# main.net
KiCad netlist of a schematic drawn in EAGLE
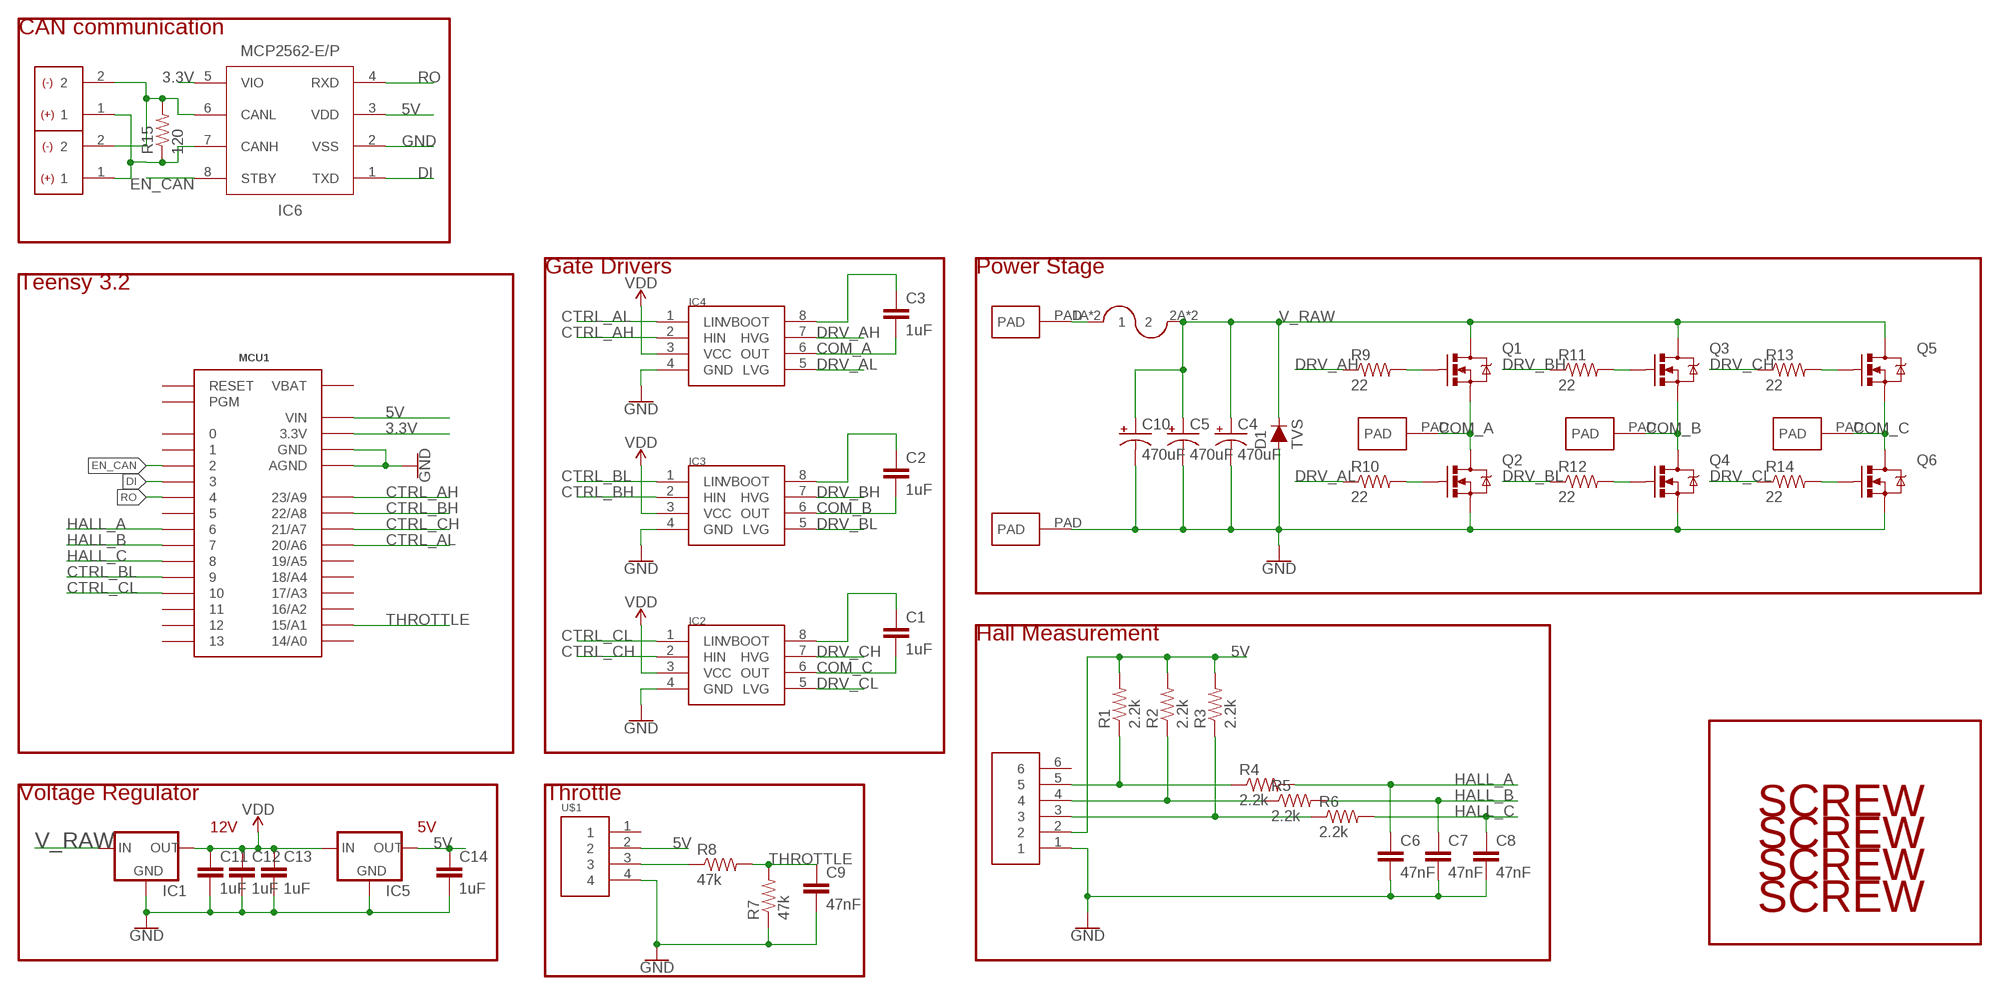
[diagram p0: schematic, sheet 1]

(export (version "E")
  (design (tool "Eeschema 10.0.6"))
  (components
    (comp (ref "C1")
      (value "1uF")
      (footprint "eagle-import:CAP-PTH-SMALL-KIT")
      (libsource (lib "eagle-import") (part "CAPKIT"))
    )
    (comp (ref "C2")
      (value "1uF")
      (footprint "eagle-import:CAP-PTH-SMALL-KIT")
      (libsource (lib "eagle-import") (part "CAPKIT"))
    )
    (comp (ref "C3")
      (value "1uF")
      (footprint "eagle-import:CAP-PTH-SMALL-KIT")
      (libsource (lib "eagle-import") (part "CAPKIT"))
    )
    (comp (ref "C4")
      (value "470uF")
      (footprint "eagle-import:CPOL-RADIAL-5MM-10MM")
      (libsource (lib "eagle-import") (part "1000UF-RADIAL-5MM-25V-20%"))
    )
    (comp (ref "C5")
      (value "470uF")
      (footprint "eagle-import:CPOL-RADIAL-5MM-10MM")
      (libsource (lib "eagle-import") (part "1000UF-RADIAL-5MM-25V-20%"))
    )
    (comp (ref "C6")
      (value "47nF")
      (footprint "eagle-import:CAP-PTH-SMALL-KIT")
      (libsource (lib "eagle-import") (part "CAPKIT"))
    )
    (comp (ref "C7")
      (value "47nF")
      (footprint "eagle-import:CAP-PTH-SMALL-KIT")
      (libsource (lib "eagle-import") (part "CAPKIT"))
    )
    (comp (ref "C8")
      (value "47nF")
      (footprint "eagle-import:CAP-PTH-SMALL-KIT")
      (libsource (lib "eagle-import") (part "CAPKIT"))
    )
    (comp (ref "C9")
      (value "47nF")
      (footprint "eagle-import:CAP-PTH-SMALL-KIT")
      (libsource (lib "eagle-import") (part "CAPKIT"))
    )
    (comp (ref "C10")
      (value "470uF")
      (footprint "eagle-import:CPOL-RADIAL-5MM-10MM")
      (libsource (lib "eagle-import") (part "1000UF-RADIAL-5MM-25V-20%"))
    )
    (comp (ref "C11")
      (value "1uF")
      (footprint "eagle-import:CAP-PTH-SMALL-KIT")
      (libsource (lib "eagle-import") (part "CAPKIT"))
    )
    (comp (ref "C12")
      (value "1uF")
      (footprint "eagle-import:CAP-PTH-SMALL-KIT")
      (libsource (lib "eagle-import") (part "CAPKIT"))
    )
    (comp (ref "C13")
      (value "1uF")
      (footprint "eagle-import:CAP-PTH-SMALL-KIT")
      (libsource (lib "eagle-import") (part "CAPKIT"))
    )
    (comp (ref "C14")
      (value "1uF")
      (footprint "eagle-import:CAP-PTH-SMALL-KIT")
      (libsource (lib "eagle-import") (part "CAPKIT"))
    )
    (comp (ref "CAN1")
      (value "HEADER2")
      (footprint "eagle-import:2PINVALULOK")
      (libsource (lib "eagle-import") (part "HEADER2"))
    )
    (comp (ref "CAN2")
      (value "HEADER2")
      (footprint "eagle-import:2PINVALULOK")
      (libsource (lib "eagle-import") (part "HEADER2"))
    )
    (comp (ref "D1")
      (value "TVS")
      (footprint "eagle-import:DIODE-1N4001")
      (libsource (lib "eagle-import") (part "DIODE-PTH"))
    )
    (comp (ref "IC1")
      (value "V_REG_78XX")
      (footprint "eagle-import:V78W_BACKWARDS")
      (libsource (lib "eagle-import") (part "V_REG_78XX"))
    )
    (comp (ref "IC2")
      (value "L6387EDIP8")
      (footprint "eagle-import:DIP762W53P254L1092H508Q8B")
      (libsource (lib "eagle-import") (part "L6387EDIP8"))
    )
    (comp (ref "IC3")
      (value "L6387EDIP8")
      (footprint "eagle-import:DIP762W53P254L1092H508Q8B")
      (libsource (lib "eagle-import") (part "L6387EDIP8"))
    )
    (comp (ref "IC4")
      (value "L6387EDIP8")
      (footprint "eagle-import:DIP762W53P254L1092H508Q8B")
      (libsource (lib "eagle-import") (part "L6387EDIP8"))
    )
    (comp (ref "IC5")
      (value "V_REG_78XXTO-92_UNTESTED")
      (footprint "eagle-import:TO-92")
      (libsource (lib "eagle-import") (part "SparkFun-IC-Power_V_REG_78XXTO-92_UNTESTED"))
    )
    (comp (ref "IC6")
      (value "MCP2562-E/P")
      (footprint "eagle-import:PDIP8_300MC")
      (fields (field (name "MANUFACTURER_PART_NUMBER") "MCP2562EP"))
      (libsource (lib "eagle-import") (part "MCP2562-E/P"))
    )
    (comp (ref "J3")
      (value "FUSE")
      (footprint "eagle-import:AUTO_FUSE")
      (libsource (lib "eagle-import") (part "FUSE"))
    )
    (comp (ref "MCU1")
      (value "TEENSY_3.0_BASIC")
      (footprint "eagle-import:TEENSY_3.0_BASIC")
      (libsource (lib "eagle-import") (part "TEENSY_3.0_BASIC"))
    )
    (comp (ref "Q1")
      (value "MOSFET-NCHANNELTO-220-FLAT")
      (footprint "eagle-import:TO-220-FLAT")
      (libsource (lib "eagle-import") (part "MOSFET-NCHANNELTO-220-FLAT"))
    )
    (comp (ref "Q2")
      (value "MOSFET-NCHANNELTO-220-FLAT")
      (footprint "eagle-import:TO-220-FLAT")
      (libsource (lib "eagle-import") (part "MOSFET-NCHANNELTO-220-FLAT"))
    )
    (comp (ref "Q3")
      (value "MOSFET-NCHANNELTO-220-FLAT")
      (footprint "eagle-import:TO-220-FLAT")
      (libsource (lib "eagle-import") (part "MOSFET-NCHANNELTO-220-FLAT"))
    )
    (comp (ref "Q4")
      (value "MOSFET-NCHANNELTO-220-FLAT")
      (footprint "eagle-import:TO-220-FLAT")
      (libsource (lib "eagle-import") (part "MOSFET-NCHANNELTO-220-FLAT"))
    )
    (comp (ref "Q5")
      (value "MOSFET-NCHANNELTO-220-FLAT")
      (footprint "eagle-import:TO-220-FLAT")
      (libsource (lib "eagle-import") (part "MOSFET-NCHANNELTO-220-FLAT"))
    )
    (comp (ref "Q6")
      (value "MOSFET-NCHANNELTO-220-FLAT")
      (footprint "eagle-import:TO-220-FLAT")
      (libsource (lib "eagle-import") (part "MOSFET-NCHANNELTO-220-FLAT"))
    )
    (comp (ref "R1")
      (value "2.2k")
      (footprint "eagle-import:AXIAL-0.3")
      (libsource (lib "eagle-import") (part "RESISTORAXIAL-0.3"))
    )
    (comp (ref "R2")
      (value "2.2k")
      (footprint "eagle-import:AXIAL-0.3")
      (libsource (lib "eagle-import") (part "RESISTORAXIAL-0.3"))
    )
    (comp (ref "R3")
      (value "2.2k")
      (footprint "eagle-import:AXIAL-0.3")
      (libsource (lib "eagle-import") (part "RESISTORAXIAL-0.3"))
    )
    (comp (ref "R4")
      (value "2.2k")
      (footprint "eagle-import:AXIAL-0.3")
      (libsource (lib "eagle-import") (part "RESISTORAXIAL-0.3"))
    )
    (comp (ref "R5")
      (value "2.2k")
      (footprint "eagle-import:AXIAL-0.3")
      (libsource (lib "eagle-import") (part "RESISTORAXIAL-0.3"))
    )
    (comp (ref "R6")
      (value "2.2k")
      (footprint "eagle-import:AXIAL-0.3")
      (libsource (lib "eagle-import") (part "RESISTORAXIAL-0.3"))
    )
    (comp (ref "R7")
      (value "47k")
      (footprint "eagle-import:AXIAL-0.3")
      (libsource (lib "eagle-import") (part "RESISTORAXIAL-0.3"))
    )
    (comp (ref "R8")
      (value "47k")
      (footprint "eagle-import:AXIAL-0.3")
      (libsource (lib "eagle-import") (part "RESISTORAXIAL-0.3"))
    )
    (comp (ref "R9")
      (value "22")
      (footprint "eagle-import:AXIAL-0.3")
      (libsource (lib "eagle-import") (part "RESISTORAXIAL-0.3"))
    )
    (comp (ref "R10")
      (value "22")
      (footprint "eagle-import:AXIAL-0.3")
      (libsource (lib "eagle-import") (part "RESISTORAXIAL-0.3"))
    )
    (comp (ref "R11")
      (value "22")
      (footprint "eagle-import:AXIAL-0.3")
      (libsource (lib "eagle-import") (part "RESISTORAXIAL-0.3"))
    )
    (comp (ref "R12")
      (value "22")
      (footprint "eagle-import:AXIAL-0.3")
      (libsource (lib "eagle-import") (part "RESISTORAXIAL-0.3"))
    )
    (comp (ref "R13")
      (value "22")
      (footprint "eagle-import:AXIAL-0.3")
      (libsource (lib "eagle-import") (part "RESISTORAXIAL-0.3"))
    )
    (comp (ref "R14")
      (value "22")
      (footprint "eagle-import:AXIAL-0.3")
      (libsource (lib "eagle-import") (part "RESISTORAXIAL-0.3"))
    )
    (comp (ref "R15")
      (value "120")
      (footprint "eagle-import:AXIAL-0.3")
      (libsource (lib "eagle-import") (part "RESISTORAXIAL-0.3"))
    )
    (comp (ref "U$1")
      (value "HEADER4VALULOK")
      (footprint "eagle-import:4PINVALULOK")
      (libsource (lib "eagle-import") (part "HEADER4VALULOK"))
    )
    (comp (ref "U$2")
      (value "HEADER6")
      (footprint "eagle-import:6PINVALULOK")
      (libsource (lib "eagle-import") (part "HEADER6"))
    )
    (comp (ref "U$4")
      (value "PAD")
      (footprint "eagle-import:PAD")
      (libsource (lib "eagle-import") (part "PAD"))
    )
    (comp (ref "U$5")
      (value "PAD")
      (footprint "eagle-import:PAD")
      (libsource (lib "eagle-import") (part "PAD"))
    )
    (comp (ref "U$6")
      (value "PAD")
      (footprint "eagle-import:PAD")
      (libsource (lib "eagle-import") (part "PAD"))
    )
    (comp (ref "U$7")
      (value "PAD")
      (footprint "eagle-import:PAD")
      (libsource (lib "eagle-import") (part "PAD"))
    )
    (comp (ref "U$8")
      (value "PAD")
      (footprint "eagle-import:PAD")
      (libsource (lib "eagle-import") (part "PAD"))
    )
    (comp (ref "U$10")
      (value "SCREW")
      (footprint "eagle-import:M3HOLE")
      (libsource (lib "eagle-import") (part "SCREW"))
    )
    (comp (ref "U$11")
      (value "SCREW")
      (footprint "eagle-import:M3HOLE")
      (libsource (lib "eagle-import") (part "SCREW"))
    )
    (comp (ref "U$12")
      (value "SCREW")
      (footprint "eagle-import:M3HOLE")
      (libsource (lib "eagle-import") (part "SCREW"))
    )
    (comp (ref "U$13")
      (value "SCREW")
      (footprint "eagle-import:M3HOLE")
      (libsource (lib "eagle-import") (part "SCREW"))
    )
  )
  (nets
    (net (code "1") (name "/3.3V") (class "Default")
      (node (ref "IC6") (pin "5") (pinfunction "VIO_5") (pintype "passive"))
      (node (ref "MCU1") (pin "3.3V") (pinfunction "3.3V_3.3V") (pintype "power_in"))
      (node (ref "MCU1") (pin "3.3V1") (pinfunction "3.3V_3.3V1") (pintype "power_in"))
    )
    (net (code "2") (name "/5V") (class "Default")
      (node (ref "C14") (pin "1") (pinfunction "1_1") (pintype "passive"))
      (node (ref "IC5") (pin "1") (pinfunction "OUT_1") (pintype "passive"))
      (node (ref "IC6") (pin "3") (pinfunction "VDD_3") (pintype "power_in"))
      (node (ref "MCU1") (pin "VIN") (pinfunction "VIN_VIN") (pintype "power_in"))
      (node (ref "R1") (pin "P$2") (pinfunction "2_P$2") (pintype "passive"))
      (node (ref "R2") (pin "P$2") (pinfunction "2_P$2") (pintype "passive"))
      (node (ref "R3") (pin "P$2") (pinfunction "2_P$2") (pintype "passive"))
      (node (ref "U$1") (pin "2") (pinfunction "2_2") (pintype "bidirectional"))
      (node (ref "U$2") (pin "2") (pinfunction "2_2") (pintype "bidirectional"))
    )
    (net (code "3") (name "/COM_A") (class "Default")
      (node (ref "C3") (pin "2") (pinfunction "2_2") (pintype "passive"))
      (node (ref "IC4") (pin "6") (pinfunction "OUT_6") (pintype "bidirectional"))
      (node (ref "Q1") (pin "3") (pinfunction "S_3") (pintype "passive"))
      (node (ref "Q2") (pin "2") (pinfunction "D_2") (pintype "passive"))
      (node (ref "Q2") (pin "PAD") (pinfunction "D_PAD") (pintype "passive"))
      (node (ref "U$6") (pin "PAD") (pinfunction "PAD_PAD") (pintype "bidirectional"))
    )
    (net (code "4") (name "/COM_B") (class "Default")
      (node (ref "C2") (pin "2") (pinfunction "2_2") (pintype "passive"))
      (node (ref "IC3") (pin "6") (pinfunction "OUT_6") (pintype "bidirectional"))
      (node (ref "Q3") (pin "3") (pinfunction "S_3") (pintype "passive"))
      (node (ref "Q4") (pin "2") (pinfunction "D_2") (pintype "passive"))
      (node (ref "Q4") (pin "PAD") (pinfunction "D_PAD") (pintype "passive"))
      (node (ref "U$7") (pin "PAD") (pinfunction "PAD_PAD") (pintype "bidirectional"))
    )
    (net (code "5") (name "/COM_C") (class "Default")
      (node (ref "C1") (pin "2") (pinfunction "2_2") (pintype "passive"))
      (node (ref "IC2") (pin "6") (pinfunction "OUT_6") (pintype "bidirectional"))
      (node (ref "Q5") (pin "3") (pinfunction "S_3") (pintype "passive"))
      (node (ref "Q6") (pin "2") (pinfunction "D_2") (pintype "passive"))
      (node (ref "Q6") (pin "PAD") (pinfunction "D_PAD") (pintype "passive"))
      (node (ref "U$8") (pin "PAD") (pinfunction "PAD_PAD") (pintype "bidirectional"))
    )
    (net (code "6") (name "/CTRL_AH") (class "Default")
      (node (ref "IC4") (pin "2") (pinfunction "HIN_2") (pintype "bidirectional"))
      (node (ref "MCU1") (pin "23/A9") (pinfunction "23/A9_23/A9") (pintype "bidirectional"))
    )
    (net (code "7") (name "/CTRL_AL") (class "Default")
      (node (ref "IC4") (pin "1") (pinfunction "LIN_1") (pintype "bidirectional"))
      (node (ref "MCU1") (pin "20/A6") (pinfunction "20/A6_20/A6") (pintype "bidirectional"))
    )
    (net (code "8") (name "/CTRL_BH") (class "Default")
      (node (ref "IC3") (pin "2") (pinfunction "HIN_2") (pintype "bidirectional"))
      (node (ref "MCU1") (pin "22/A8") (pinfunction "22/A8_22/A8") (pintype "bidirectional"))
    )
    (net (code "9") (name "/CTRL_BL") (class "Default")
      (node (ref "IC3") (pin "1") (pinfunction "LIN_1") (pintype "bidirectional"))
      (node (ref "MCU1") (pin "9") (pinfunction "9_9") (pintype "bidirectional"))
    )
    (net (code "10") (name "/CTRL_CH") (class "Default")
      (node (ref "IC2") (pin "2") (pinfunction "HIN_2") (pintype "bidirectional"))
      (node (ref "MCU1") (pin "21/A7") (pinfunction "21/A7_21/A7") (pintype "bidirectional"))
    )
    (net (code "11") (name "/CTRL_CL") (class "Default")
      (node (ref "IC2") (pin "1") (pinfunction "LIN_1") (pintype "bidirectional"))
      (node (ref "MCU1") (pin "10") (pinfunction "10_10") (pintype "bidirectional"))
    )
    (net (code "12") (name "/DRV_AH") (class "Default")
      (node (ref "IC4") (pin "7") (pinfunction "HVG_7") (pintype "bidirectional"))
      (node (ref "R9") (pin "P$1") (pinfunction "1_P$1") (pintype "passive"))
    )
    (net (code "13") (name "/DRV_AL") (class "Default")
      (node (ref "IC4") (pin "5") (pinfunction "LVG_5") (pintype "bidirectional"))
      (node (ref "R10") (pin "P$1") (pinfunction "1_P$1") (pintype "passive"))
    )
    (net (code "14") (name "/DRV_BH") (class "Default")
      (node (ref "IC3") (pin "7") (pinfunction "HVG_7") (pintype "bidirectional"))
      (node (ref "R11") (pin "P$1") (pinfunction "1_P$1") (pintype "passive"))
    )
    (net (code "15") (name "/DRV_BL") (class "Default")
      (node (ref "IC3") (pin "5") (pinfunction "LVG_5") (pintype "bidirectional"))
      (node (ref "R12") (pin "P$1") (pinfunction "1_P$1") (pintype "passive"))
    )
    (net (code "16") (name "/DRV_CH") (class "Default")
      (node (ref "IC2") (pin "7") (pinfunction "HVG_7") (pintype "bidirectional"))
      (node (ref "R13") (pin "P$1") (pinfunction "1_P$1") (pintype "passive"))
    )
    (net (code "17") (name "/DRV_CL") (class "Default")
      (node (ref "IC2") (pin "5") (pinfunction "LVG_5") (pintype "bidirectional"))
      (node (ref "R14") (pin "P$1") (pinfunction "1_P$1") (pintype "passive"))
    )
    (net (code "18") (name "/HALL_A") (class "Default")
      (node (ref "C6") (pin "1") (pinfunction "1_1") (pintype "passive"))
      (node (ref "MCU1") (pin "6") (pinfunction "6_6") (pintype "bidirectional"))
      (node (ref "R4") (pin "P$2") (pinfunction "2_P$2") (pintype "passive"))
    )
    (net (code "19") (name "/HALL_B") (class "Default")
      (node (ref "C7") (pin "1") (pinfunction "1_1") (pintype "passive"))
      (node (ref "MCU1") (pin "7") (pinfunction "7_7") (pintype "bidirectional"))
      (node (ref "R5") (pin "P$2") (pinfunction "2_P$2") (pintype "passive"))
    )
    (net (code "20") (name "/HALL_C") (class "Default")
      (node (ref "C8") (pin "1") (pinfunction "1_1") (pintype "passive"))
      (node (ref "MCU1") (pin "8") (pinfunction "8_8") (pintype "bidirectional"))
      (node (ref "R6") (pin "P$2") (pinfunction "2_P$2") (pintype "passive"))
    )
    (net (code "21") (name "/THROTTLE") (class "Default")
      (node (ref "C9") (pin "1") (pinfunction "1_1") (pintype "passive"))
      (node (ref "MCU1") (pin "15/A1") (pinfunction "15/A1_15/A1") (pintype "bidirectional"))
      (node (ref "R7") (pin "P$2") (pinfunction "2_P$2") (pintype "passive"))
      (node (ref "R8") (pin "P$2") (pinfunction "2_P$2") (pintype "passive"))
    )
    (net (code "22") (name "/VBAT") (class "Default")
      (node (ref "MCU1") (pin "VBAT") (pinfunction "VBAT_VBAT") (pintype "power_in"))
    )
    (net (code "23") (name "/V_RAW") (class "Default")
      (node (ref "C10") (pin "+") (pinfunction "+_+") (pintype "passive"))
      (node (ref "C4") (pin "+") (pinfunction "+_+") (pintype "passive"))
      (node (ref "C5") (pin "+") (pinfunction "+_+") (pintype "passive"))
      (node (ref "D1") (pin "C") (pinfunction "C_C") (pintype "passive"))
      (node (ref "IC1") (pin "IN") (pinfunction "IN_IN") (pintype "input"))
      (node (ref "J3") (pin "2A") (pinfunction "2_2A") (pintype "bidirectional"))
      (node (ref "J3") (pin "2B") (pinfunction "2_2B") (pintype "bidirectional"))
      (node (ref "Q1") (pin "2") (pinfunction "D_2") (pintype "passive"))
      (node (ref "Q1") (pin "PAD") (pinfunction "D_PAD") (pintype "passive"))
      (node (ref "Q3") (pin "2") (pinfunction "D_2") (pintype "passive"))
      (node (ref "Q3") (pin "PAD") (pinfunction "D_PAD") (pintype "passive"))
      (node (ref "Q5") (pin "2") (pinfunction "D_2") (pintype "passive"))
      (node (ref "Q5") (pin "PAD") (pinfunction "D_PAD") (pintype "passive"))
    )
    (net (code "24") (name "DI") (class "Default")
      (node (ref "IC6") (pin "1") (pinfunction "TXD_1") (pintype "input"))
      (node (ref "MCU1") (pin "3") (pinfunction "3_3") (pintype "bidirectional"))
    )
    (net (code "25") (name "EN_CAN") (class "Default")
      (node (ref "IC6") (pin "8") (pinfunction "STBY_8") (pintype "input"))
      (node (ref "MCU1") (pin "2") (pinfunction "2_2") (pintype "bidirectional"))
    )
    (net (code "26") (name "GND") (class "Default")
      (node (ref "C10") (pin "-") (pinfunction "-_-") (pintype "passive"))
      (node (ref "C11") (pin "2") (pinfunction "2_2") (pintype "passive"))
      (node (ref "C12") (pin "2") (pinfunction "2_2") (pintype "passive"))
      (node (ref "C13") (pin "2") (pinfunction "2_2") (pintype "passive"))
      (node (ref "C14") (pin "2") (pinfunction "2_2") (pintype "passive"))
      (node (ref "C4") (pin "-") (pinfunction "-_-") (pintype "passive"))
      (node (ref "C5") (pin "-") (pinfunction "-_-") (pintype "passive"))
      (node (ref "C6") (pin "2") (pinfunction "2_2") (pintype "passive"))
      (node (ref "C7") (pin "2") (pinfunction "2_2") (pintype "passive"))
      (node (ref "C8") (pin "2") (pinfunction "2_2") (pintype "passive"))
      (node (ref "C9") (pin "2") (pinfunction "2_2") (pintype "passive"))
      (node (ref "D1") (pin "A") (pinfunction "A_A") (pintype "passive"))
      (node (ref "IC1") (pin "GND") (pinfunction "GND_GND") (pintype "input"))
      (node (ref "IC2") (pin "4") (pinfunction "GND_4") (pintype "bidirectional"))
      (node (ref "IC3") (pin "4") (pinfunction "GND_4") (pintype "bidirectional"))
      (node (ref "IC4") (pin "4") (pinfunction "GND_4") (pintype "bidirectional"))
      (node (ref "IC5") (pin "2") (pinfunction "GND_2") (pintype "input"))
      (node (ref "IC6") (pin "2") (pinfunction "VSS_2") (pintype "power_in"))
      (node (ref "MCU1") (pin "AGND") (pinfunction "AGND_AGND") (pintype "power_in"))
      (node (ref "MCU1") (pin "GND") (pinfunction "GND_GND") (pintype "power_in"))
      (node (ref "MCU1") (pin "GND1") (pinfunction "GND_GND1") (pintype "power_in"))
      (node (ref "Q2") (pin "3") (pinfunction "S_3") (pintype "passive"))
      (node (ref "Q4") (pin "3") (pinfunction "S_3") (pintype "passive"))
      (node (ref "Q6") (pin "3") (pinfunction "S_3") (pintype "passive"))
      (node (ref "R7") (pin "P$1") (pinfunction "1_P$1") (pintype "passive"))
      (node (ref "U$1") (pin "4") (pinfunction "4_4") (pintype "bidirectional"))
      (node (ref "U$2") (pin "1") (pinfunction "1_1") (pintype "bidirectional"))
      (node (ref "U$5") (pin "PAD") (pinfunction "PAD_PAD") (pintype "bidirectional"))
    )
    (net (code "27") (name "Net-(IC2-VBOOT)") (class "Default")
      (node (ref "C1") (pin "1") (pinfunction "1_1") (pintype "passive"))
      (node (ref "IC2") (pin "8") (pinfunction "VBOOT_8") (pintype "bidirectional"))
    )
    (net (code "28") (name "Net-(IC3-VBOOT)") (class "Default")
      (node (ref "C2") (pin "1") (pinfunction "1_1") (pintype "passive"))
      (node (ref "IC3") (pin "8") (pinfunction "VBOOT_8") (pintype "bidirectional"))
    )
    (net (code "29") (name "Net-(IC4-VBOOT)") (class "Default")
      (node (ref "C3") (pin "1") (pinfunction "1_1") (pintype "passive"))
      (node (ref "IC4") (pin "8") (pinfunction "VBOOT_8") (pintype "bidirectional"))
    )
    (net (code "30") (name "Net-(IC6-CANH)") (class "Default")
      (node (ref "CAN1") (pin "1") (pinfunction "1_1") (pintype "bidirectional"))
      (node (ref "CAN2") (pin "1") (pinfunction "1_1") (pintype "bidirectional"))
      (node (ref "IC6") (pin "7") (pinfunction "CANH_7") (pintype "bidirectional"))
      (node (ref "R15") (pin "P$1") (pinfunction "1_P$1") (pintype "passive"))
    )
    (net (code "31") (name "Net-(IC6-CANL)") (class "Default")
      (node (ref "CAN1") (pin "2") (pinfunction "2_2") (pintype "bidirectional"))
      (node (ref "CAN2") (pin "2") (pinfunction "2_2") (pintype "bidirectional"))
      (node (ref "IC6") (pin "6") (pinfunction "CANL_6") (pintype "bidirectional"))
      (node (ref "R15") (pin "P$2") (pinfunction "2_P$2") (pintype "passive"))
    )
    (net (code "32") (name "Net-(J3-1-Pad1A)") (class "Default")
      (node (ref "J3") (pin "1A") (pinfunction "1_1A") (pintype "bidirectional"))
      (node (ref "J3") (pin "1B") (pinfunction "1_1B") (pintype "bidirectional"))
      (node (ref "U$4") (pin "PAD") (pinfunction "PAD_PAD") (pintype "bidirectional"))
    )
    (net (code "33") (name "Net-(Q1-G)") (class "Default")
      (node (ref "Q1") (pin "1") (pinfunction "G_1") (pintype "passive"))
      (node (ref "R9") (pin "P$2") (pinfunction "2_P$2") (pintype "passive"))
    )
    (net (code "34") (name "Net-(Q2-G)") (class "Default")
      (node (ref "Q2") (pin "1") (pinfunction "G_1") (pintype "passive"))
      (node (ref "R10") (pin "P$2") (pinfunction "2_P$2") (pintype "passive"))
    )
    (net (code "35") (name "Net-(Q3-G)") (class "Default")
      (node (ref "Q3") (pin "1") (pinfunction "G_1") (pintype "passive"))
      (node (ref "R11") (pin "P$2") (pinfunction "2_P$2") (pintype "passive"))
    )
    (net (code "36") (name "Net-(Q4-G)") (class "Default")
      (node (ref "Q4") (pin "1") (pinfunction "G_1") (pintype "passive"))
      (node (ref "R12") (pin "P$2") (pinfunction "2_P$2") (pintype "passive"))
    )
    (net (code "37") (name "Net-(Q5-G)") (class "Default")
      (node (ref "Q5") (pin "1") (pinfunction "G_1") (pintype "passive"))
      (node (ref "R13") (pin "P$2") (pinfunction "2_P$2") (pintype "passive"))
    )
    (net (code "38") (name "Net-(Q6-G)") (class "Default")
      (node (ref "Q6") (pin "1") (pinfunction "G_1") (pintype "passive"))
      (node (ref "R14") (pin "P$2") (pinfunction "2_P$2") (pintype "passive"))
    )
    (net (code "39") (name "Net-(R1-1)") (class "Default")
      (node (ref "R1") (pin "P$1") (pinfunction "1_P$1") (pintype "passive"))
      (node (ref "R4") (pin "P$1") (pinfunction "1_P$1") (pintype "passive"))
      (node (ref "U$2") (pin "5") (pinfunction "5_5") (pintype "bidirectional"))
    )
    (net (code "40") (name "Net-(R2-1)") (class "Default")
      (node (ref "R2") (pin "P$1") (pinfunction "1_P$1") (pintype "passive"))
      (node (ref "R5") (pin "P$1") (pinfunction "1_P$1") (pintype "passive"))
      (node (ref "U$2") (pin "4") (pinfunction "4_4") (pintype "bidirectional"))
    )
    (net (code "41") (name "Net-(R3-1)") (class "Default")
      (node (ref "R3") (pin "P$1") (pinfunction "1_P$1") (pintype "passive"))
      (node (ref "R6") (pin "P$1") (pinfunction "1_P$1") (pintype "passive"))
      (node (ref "U$2") (pin "3") (pinfunction "3_3") (pintype "bidirectional"))
    )
    (net (code "42") (name "Net-(R8-1)") (class "Default")
      (node (ref "R8") (pin "P$1") (pinfunction "1_P$1") (pintype "passive"))
      (node (ref "U$1") (pin "3") (pinfunction "3_3") (pintype "bidirectional"))
    )
    (net (code "43") (name "RO") (class "Default")
      (node (ref "IC6") (pin "4") (pinfunction "RXD_4") (pintype "output"))
      (node (ref "MCU1") (pin "4") (pinfunction "4_4") (pintype "bidirectional"))
    )
    (net (code "44") (name "VDD") (class "Default")
      (node (ref "C11") (pin "1") (pinfunction "1_1") (pintype "passive"))
      (node (ref "C12") (pin "1") (pinfunction "1_1") (pintype "passive"))
      (node (ref "C13") (pin "1") (pinfunction "1_1") (pintype "passive"))
      (node (ref "IC1") (pin "OUT") (pinfunction "OUT_OUT") (pintype "output"))
      (node (ref "IC2") (pin "3") (pinfunction "VCC_3") (pintype "bidirectional"))
      (node (ref "IC3") (pin "3") (pinfunction "VCC_3") (pintype "bidirectional"))
      (node (ref "IC4") (pin "3") (pinfunction "VCC_3") (pintype "bidirectional"))
      (node (ref "IC5") (pin "3") (pinfunction "IN_3") (pintype "input"))
    )
    (net (code "45") (name "unconnected-(MCU1-Pad0)") (class "Default")
      (node (ref "MCU1") (pin "0") (pinfunction "0_0") (pintype "bidirectional"))
    )
    (net (code "46") (name "unconnected-(MCU1-Pad1)") (class "Default")
      (node (ref "MCU1") (pin "1") (pinfunction "1_1") (pintype "bidirectional"))
    )
    (net (code "47") (name "unconnected-(MCU1-Pad5)") (class "Default")
      (node (ref "MCU1") (pin "5") (pinfunction "5_5") (pintype "bidirectional"))
    )
    (net (code "48") (name "unconnected-(MCU1-Pad11)") (class "Default")
      (node (ref "MCU1") (pin "11") (pinfunction "11_11") (pintype "bidirectional"))
    )
    (net (code "49") (name "unconnected-(MCU1-Pad12)") (class "Default")
      (node (ref "MCU1") (pin "12") (pinfunction "12_12") (pintype "bidirectional"))
    )
    (net (code "50") (name "unconnected-(MCU1-Pad13)") (class "Default")
      (node (ref "MCU1") (pin "13") (pinfunction "13_13") (pintype "bidirectional"))
    )
    (net (code "51") (name "unconnected-(MCU1-Pad14{slash}A0)") (class "Default")
      (node (ref "MCU1") (pin "14/A0") (pinfunction "14/A0_14/A0") (pintype "bidirectional"))
    )
    (net (code "52") (name "unconnected-(MCU1-Pad16{slash}A2)") (class "Default")
      (node (ref "MCU1") (pin "16/A2") (pinfunction "16/A2_16/A2") (pintype "bidirectional"))
    )
    (net (code "53") (name "unconnected-(MCU1-Pad17{slash}A3)") (class "Default")
      (node (ref "MCU1") (pin "17/A3") (pinfunction "17/A3_17/A3") (pintype "bidirectional"))
    )
    (net (code "54") (name "unconnected-(MCU1-Pad18{slash}A4)") (class "Default")
      (node (ref "MCU1") (pin "18/A4") (pinfunction "18/A4_18/A4") (pintype "bidirectional"))
    )
    (net (code "55") (name "unconnected-(MCU1-Pad19{slash}A5)") (class "Default")
      (node (ref "MCU1") (pin "19/A5") (pinfunction "19/A5_19/A5") (pintype "bidirectional"))
    )
    (net (code "56") (name "unconnected-(MCU1-PadPGM)") (class "Default")
      (node (ref "MCU1") (pin "PGM") (pinfunction "PGM_PGM") (pintype "bidirectional"))
    )
    (net (code "57") (name "unconnected-(MCU1-PadRESET)") (class "Default")
      (node (ref "MCU1") (pin "RESET") (pinfunction "RESET_RESET") (pintype "bidirectional"))
    )
    (net (code "58") (name "unconnected-(U$1-Pad1)") (class "Default")
      (node (ref "U$1") (pin "1") (pinfunction "1_1") (pintype "bidirectional"))
    )
    (net (code "59") (name "unconnected-(U$2-Pad6)") (class "Default")
      (node (ref "U$2") (pin "6") (pinfunction "6_6") (pintype "bidirectional"))
    )
  )
)
